# accelerator.net
KiCad netlist of a schematic drawn in Altium Designer
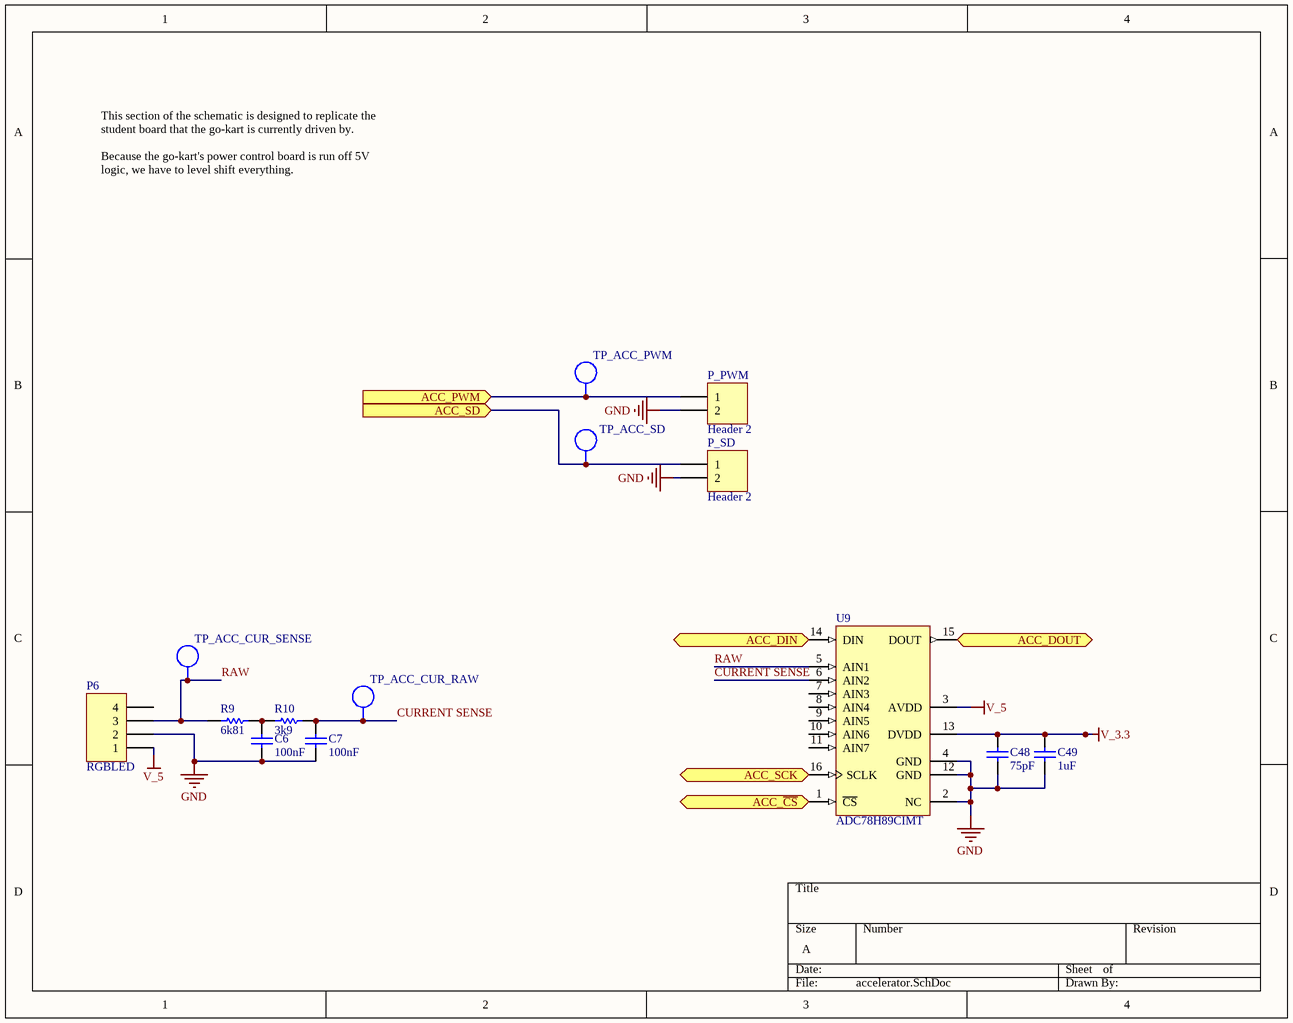
[diagram p0: accelerator.SchDoc]

(export (version "E")
  (design (tool "Eeschema 10.0.6"))
  (components
    (comp (ref "C6")
      (value "100nF")
      (footprint "0603")
      (description "CAP CER .10UF 50V X5R 0603")
      (fields (field (name "MANUFACTURER") "Taiyo Yuden") (field (name "PART NUMBER") "CP_100nF 0603"))
      (libsource (lib "ENEL429_4") (part "CP_100nF 0603"))
    )
    (comp (ref "C7")
      (value "100nF")
      (footprint "0603")
      (description "CAP CER .10UF 50V X5R 0603")
      (fields (field (name "MANUFACTURER") "Taiyo Yuden") (field (name "PART NUMBER") "CP_100nF 0603"))
      (libsource (lib "ENEL429_4") (part "CP_100nF 0603"))
    )
    (comp (ref "C48")
      (value "75pF")
      (footprint "0603")
      (description "CAP CER 75PF 50V 5% C0G 0603")
      (fields (field (name "MANUFACTURER") "Murata Electronics") (field (name "PART NUMBER") "CP_75pF 0603"))
      (libsource (lib "ENEL429_4") (part "CP_75pF 0603"))
    )
    (comp (ref "C49")
      (value "1uF")
      (footprint "0603")
      (description "CAP CER 1.0UF 50V X7R 0603")
      (fields (field (name "MANUFACTURER") "Taiyo Yuden") (field (name "PART NUMBER") "CP_1uF_50V_0603"))
      (libsource (lib "ENEL429_4") (part "CP_1uF_50V_0603"))
    )
    (comp (ref "P6")
      (value "RGBLED")
      (footprint "HDR1X4")
      (description "Header, 4-Pin")
      (fields (field (name "PUBLISHER") "Altium Limited"))
      (libsource (lib "Miscellaneous Connectors") (part "Header 4"))
    )
    (comp (ref "P_PWM")
      (value "Header 2")
      (footprint "HDR1X2")
      (description "Header, 2-Pin")
      (fields (field (name "PUBLISHER") "Altium Limited"))
      (libsource (lib "Miscellaneous Connectors") (part "Header 2"))
    )
    (comp (ref "P_SD")
      (value "Header 2")
      (footprint "HDR1X2")
      (description "Header, 2-Pin")
      (fields (field (name "PUBLISHER") "Altium Limited"))
      (libsource (lib "Miscellaneous Connectors") (part "Header 2"))
    )
    (comp (ref "R9")
      (value "6k81")
      (footprint "0603")
      (description "RES 6k81 OHM 1/10W 1% 0603 SMD")
      (fields (field (name "MANUFACTURER") "Rohm") (field (name "PART NUMBER") "RS_6k81_0603"))
      (libsource (lib "ENEL429_4") (part "RS_6k81_0603"))
    )
    (comp (ref "R10")
      (value "3k9")
      (footprint "0603")
      (description "RES 3.9K OHM 1/10W 5% 0603 SMD")
      (fields (field (name "MANUFACTURER") "Yageo") (field (name "PART NUMBER") "RS_3k9 0603"))
      (libsource (lib "ENEL429_4") (part "RS_3k9 0603"))
    )
    (comp (ref "TP_ACC_CUR_RAW")
      (value "TP")
      (footprint "TEST_POINT_4X2MM")
      (description "Test-Point")
      (fields (field (name "PART NUMBER") "TP_TESTPOINT"))
      (libsource (lib "ENEL429_4") (part "TP_TESTPOINT"))
    )
    (comp (ref "TP_ACC_CUR_SENSE")
      (value "TP")
      (footprint "TEST_POINT_4X2MM")
      (description "Test-Point")
      (fields (field (name "PART NUMBER") "TP_TESTPOINT"))
      (libsource (lib "ENEL429_4") (part "TP_TESTPOINT"))
    )
    (comp (ref "TP_ACC_PWM")
      (value "TP")
      (footprint "TEST_POINT_4X2MM")
      (description "Test-Point")
      (fields (field (name "PART NUMBER") "TP_TESTPOINT"))
      (libsource (lib "ENEL429_4") (part "TP_TESTPOINT"))
    )
    (comp (ref "TP_ACC_SD")
      (value "TP")
      (footprint "TEST_POINT_4X2MM")
      (description "Test-Point")
      (fields (field (name "PART NUMBER") "TP_TESTPOINT"))
      (libsource (lib "ENEL429_4") (part "TP_TESTPOINT"))
    )
    (comp (ref "U9")
      (value "ADC78H89CIMT")
      (footprint "MTC16_N")
      (description "7-Channel, 500 KSPS, 12-Bit A/D Converter")
      (fields
        (field (name "MANUFACTURER") "National Semiconductor")
        (field (name "DIGIKEYPARTNUMBER") "ADC78H89CIMT-ND")
        (field (name "PUBLISHER") "Altium Limited")
      )
      (libsource (lib "NSC ADC") (part "ADC78H89CIMT"))
    )
  )
  (nets
    (net (code "1") (name "/ACC_DIN") (class "Default")
      (node (ref "U9") (pin "14") (pinfunction "DIN_14") (pintype "input"))
    )
    (net (code "2") (name "/ACC_DOUT") (class "Default")
      (node (ref "U9") (pin "15") (pinfunction "DOUT_15") (pintype "output"))
    )
    (net (code "3") (name "/ACC_PWM") (class "Default")
      (node (ref "P_PWM") (pin "1") (pinfunction "1_1") (pintype "passive"))
      (node (ref "TP_ACC_PWM") (pin "1") (pinfunction "1_1") (pintype "passive"))
    )
    (net (code "4") (name "/ACC_SCK") (class "Default")
      (node (ref "U9") (pin "16") (pinfunction "SCLK_16") (pintype "input"))
    )
    (net (code "5") (name "/ACC_SD") (class "Default")
      (node (ref "P_SD") (pin "1") (pinfunction "1_1") (pintype "passive"))
      (node (ref "TP_ACC_SD") (pin "1") (pinfunction "1_1") (pintype "passive"))
    )
    (net (code "6") (name "/ACC_~{CS}") (class "Default")
      (node (ref "U9") (pin "1") (pinfunction "~{CS}_1") (pintype "input"))
    )
    (net (code "7") (name "/CURRENT SENSE") (class "Default")
      (node (ref "C7") (pin "2") (pinfunction "2_2") (pintype "passive"))
      (node (ref "R10") (pin "2") (pinfunction "2_2") (pintype "passive"))
      (node (ref "TP_ACC_CUR_RAW") (pin "1") (pinfunction "1_1") (pintype "passive"))
      (node (ref "U9") (pin "6") (pinfunction "AIN2_6") (pintype "input"))
    )
    (net (code "8") (name "/RAW") (class "Default")
      (node (ref "P6") (pin "3") (pinfunction "3_3") (pintype "passive"))
      (node (ref "R9") (pin "1") (pinfunction "1_1") (pintype "passive"))
      (node (ref "TP_ACC_CUR_SENSE") (pin "1") (pinfunction "1_1") (pintype "passive"))
      (node (ref "U9") (pin "5") (pinfunction "AIN1_5") (pintype "input"))
    )
    (net (code "9") (name "GND") (class "Default")
      (node (ref "C48") (pin "1") (pinfunction "1_1") (pintype "passive"))
      (node (ref "C49") (pin "1") (pinfunction "1_1") (pintype "passive"))
      (node (ref "C6") (pin "1") (pinfunction "1_1") (pintype "passive"))
      (node (ref "C7") (pin "1") (pinfunction "1_1") (pintype "passive"))
      (node (ref "P6") (pin "2") (pinfunction "2_2") (pintype "passive"))
      (node (ref "P_PWM") (pin "2") (pinfunction "2_2") (pintype "passive"))
      (node (ref "P_SD") (pin "2") (pinfunction "2_2") (pintype "passive"))
      (node (ref "U9") (pin "12") (pinfunction "GND_12") (pintype "power_in"))
      (node (ref "U9") (pin "2") (pinfunction "NC_2") (pintype "passive"))
      (node (ref "U9") (pin "4") (pinfunction "GND_4") (pintype "power_in"))
    )
    (net (code "10") (name "Net-(C6-Pad2)") (class "Default")
      (node (ref "C6") (pin "2") (pinfunction "2_2") (pintype "passive"))
      (node (ref "R10") (pin "1") (pinfunction "1_1") (pintype "passive"))
      (node (ref "R9") (pin "2") (pinfunction "2_2") (pintype "passive"))
    )
    (net (code "11") (name "V_3.3") (class "Default")
      (node (ref "C48") (pin "2") (pinfunction "2_2") (pintype "passive"))
      (node (ref "C49") (pin "2") (pinfunction "2_2") (pintype "passive"))
      (node (ref "U9") (pin "13") (pinfunction "DVDD_13") (pintype "power_in"))
    )
    (net (code "12") (name "V_5") (class "Default")
      (node (ref "P6") (pin "1") (pinfunction "1_1") (pintype "passive"))
      (node (ref "U9") (pin "3") (pinfunction "AVDD_3") (pintype "power_in"))
    )
    (net (code "13") (name "unconnected-(P6-Pad4)") (class "Default")
      (node (ref "P6") (pin "4") (pinfunction "4_4") (pintype "passive"))
    )
    (net (code "14") (name "unconnected-(U9-AIN3-Pad7)") (class "Default")
      (node (ref "U9") (pin "7") (pinfunction "AIN3_7") (pintype "input"))
    )
    (net (code "15") (name "unconnected-(U9-AIN4-Pad8)") (class "Default")
      (node (ref "U9") (pin "8") (pinfunction "AIN4_8") (pintype "input"))
    )
    (net (code "16") (name "unconnected-(U9-AIN5-Pad9)") (class "Default")
      (node (ref "U9") (pin "9") (pinfunction "AIN5_9") (pintype "input"))
    )
    (net (code "17") (name "unconnected-(U9-AIN6-Pad10)") (class "Default")
      (node (ref "U9") (pin "10") (pinfunction "AIN6_10") (pintype "input"))
    )
    (net (code "18") (name "unconnected-(U9-AIN7-Pad11)") (class "Default")
      (node (ref "U9") (pin "11") (pinfunction "AIN7_11") (pintype "input"))
    )
  )
)
